# 1-Schematic_NFC_Business_Card.net
KiCad netlist of a schematic drawn in EasyEDA
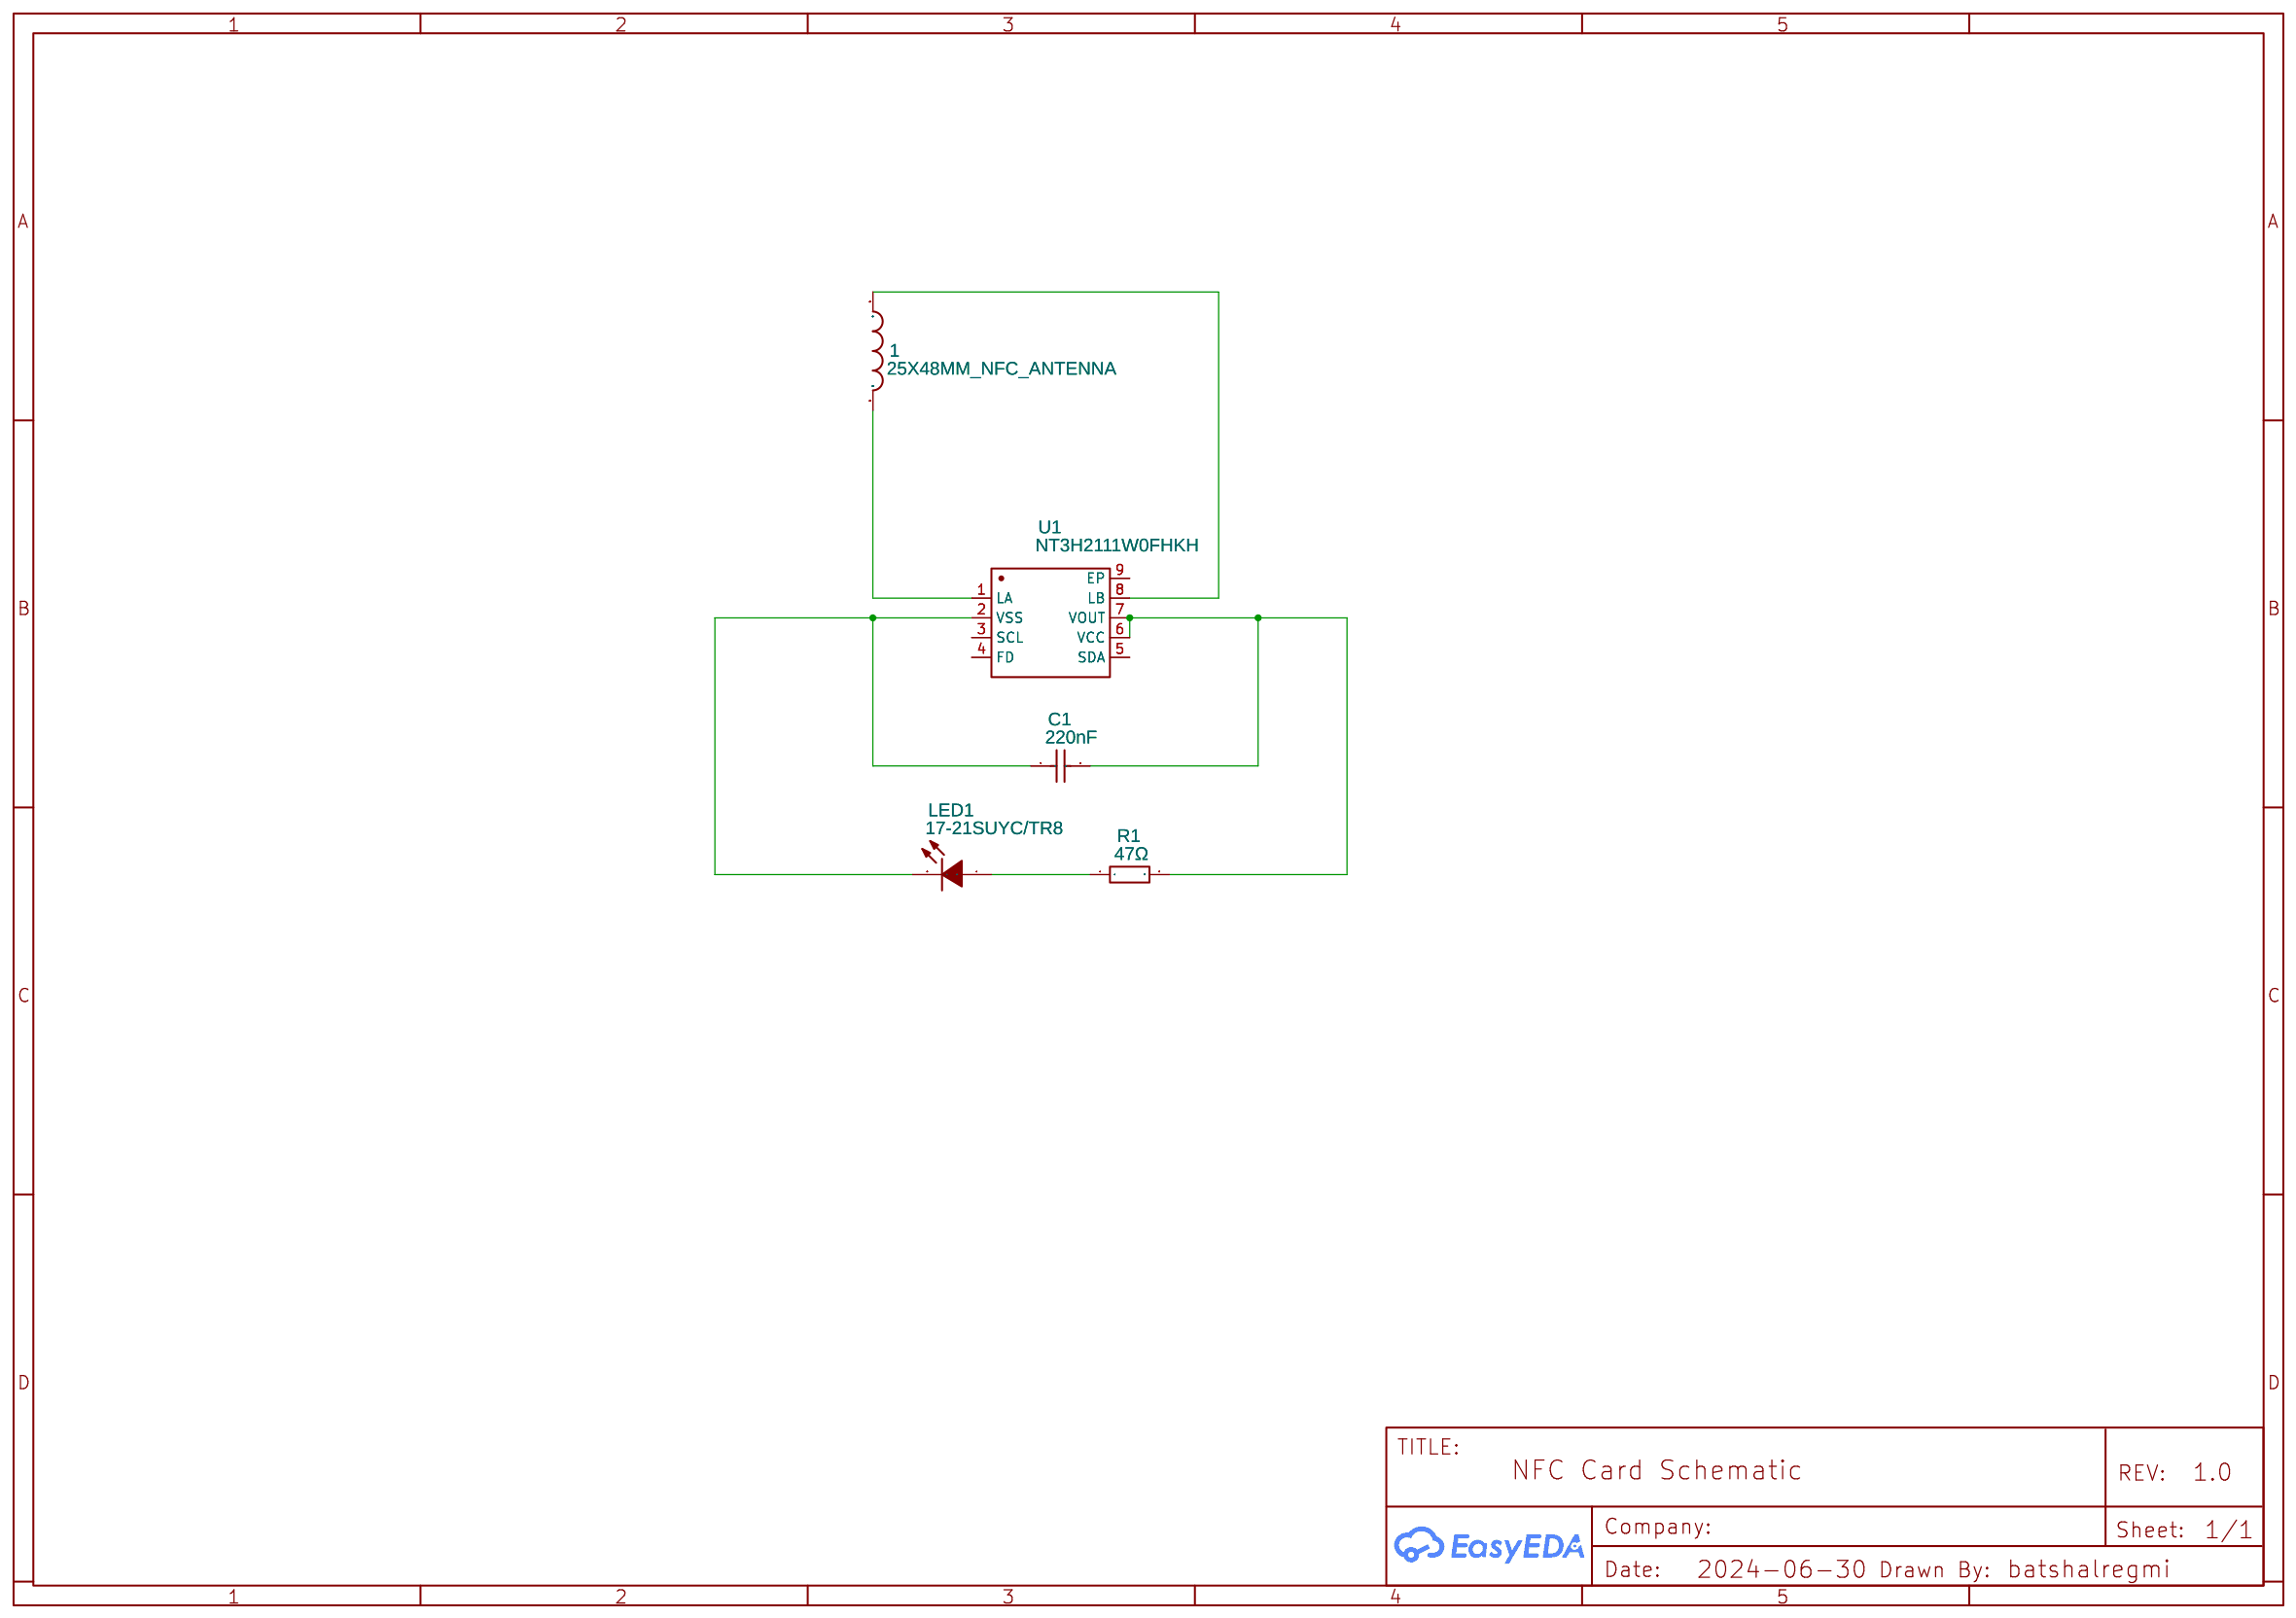
[diagram p0: schematic sheet]

(export (version "E")
  (design (tool "Eeschema 10.0.6"))
  (components
    (comp (ref "1") (value "25X48MM_NFC_ANTENNA") (libsource (lib "") (part "25X48MM_NFC_ANTENNA")))
    (comp (ref "C1")
      (value "220nF")
      (fields
        (field (name "Manufacturer Part") "CL10B224KA8NNNC")
        (field (name "Manufacturer") "SAMSUNG(三星)")
      )
      (libsource (lib "") (part "CL10B224KA8NNNC"))
    )
    (comp (ref "LED1")
      (value "17-21SUYC/TR8")
      (fields (field (name "Manufacturer Part") "KT-0805黄灯") (field (name "Manufacturer") "KENTO"))
      (libsource (lib "") (part "17-21SUYC/TR8"))
    )
    (comp (ref "R1")
      (value "47Ω")
      (fields
        (field (name "Manufacturer Part") "0603WAF470JT5E")
        (field (name "Manufacturer") "UNI-ROYAL(厚声)")
      )
      (libsource (lib "") (part "0603WAF470JT5E"))
    )
    (comp (ref "U1")
      (value "NT3H2111W0FHKH")
      (fields (field (name "Manufacturer") "NXP(恩智浦)"))
      (libsource (lib "") (part "NT3H2111W0FHKH"))
    )
  )
  (nets
    (net (code "1") (name "Net-(LED1-+)") (class "Default")
      (node (ref "LED1") (pin "1") (pinfunction "+_1") (pintype "unspecified"))
      (node (ref "R1") (pin "1") (pinfunction "1_1") (pintype "input"))
    )
    (net (code "2") (name "Net-(LED1--)") (class "Default")
      (node (ref "C1") (pin "1") (pinfunction "1_1") (pintype "input"))
      (node (ref "LED1") (pin "2") (pinfunction "-_2") (pintype "unspecified"))
      (node (ref "U1") (pin "2") (pinfunction "VSS_2") (pintype "unspecified"))
    )
    (net (code "3") (name "Net-(U1-LA)") (class "Default")
      (node (ref "1") (pin "P$2") (pinfunction "P$2_P$2") (pintype "bidirectional"))
      (node (ref "U1") (pin "1") (pinfunction "LA_1") (pintype "unspecified"))
    )
    (net (code "4") (name "Net-(U1-LB)") (class "Default")
      (node (ref "1") (pin "P$1") (pinfunction "P$1_P$1") (pintype "bidirectional"))
      (node (ref "U1") (pin "8") (pinfunction "LB_8") (pintype "unspecified"))
    )
    (net (code "5") (name "Net-(U1-VCC)") (class "Default")
      (node (ref "C1") (pin "2") (pinfunction "2_2") (pintype "input"))
      (node (ref "R1") (pin "2") (pinfunction "2_2") (pintype "input"))
      (node (ref "U1") (pin "6") (pinfunction "VCC_6") (pintype "unspecified"))
      (node (ref "U1") (pin "7") (pinfunction "VOUT_7") (pintype "unspecified"))
    )
    (net (code "6") (name "unconnected-(U1-EP-Pad9)") (class "Default")
      (node (ref "U1") (pin "9") (pinfunction "EP_9") (pintype "unspecified"))
    )
    (net (code "7") (name "unconnected-(U1-FD-Pad4)") (class "Default")
      (node (ref "U1") (pin "4") (pinfunction "FD_4") (pintype "unspecified"))
    )
    (net (code "8") (name "unconnected-(U1-SCL-Pad3)") (class "Default")
      (node (ref "U1") (pin "3") (pinfunction "SCL_3") (pintype "unspecified"))
    )
    (net (code "9") (name "unconnected-(U1-SDA-Pad5)") (class "Default")
      (node (ref "U1") (pin "5") (pinfunction "SDA_5") (pintype "unspecified"))
    )
  )
)
